# H21R20.net
KiCad netlist of a schematic drawn in EAGLE
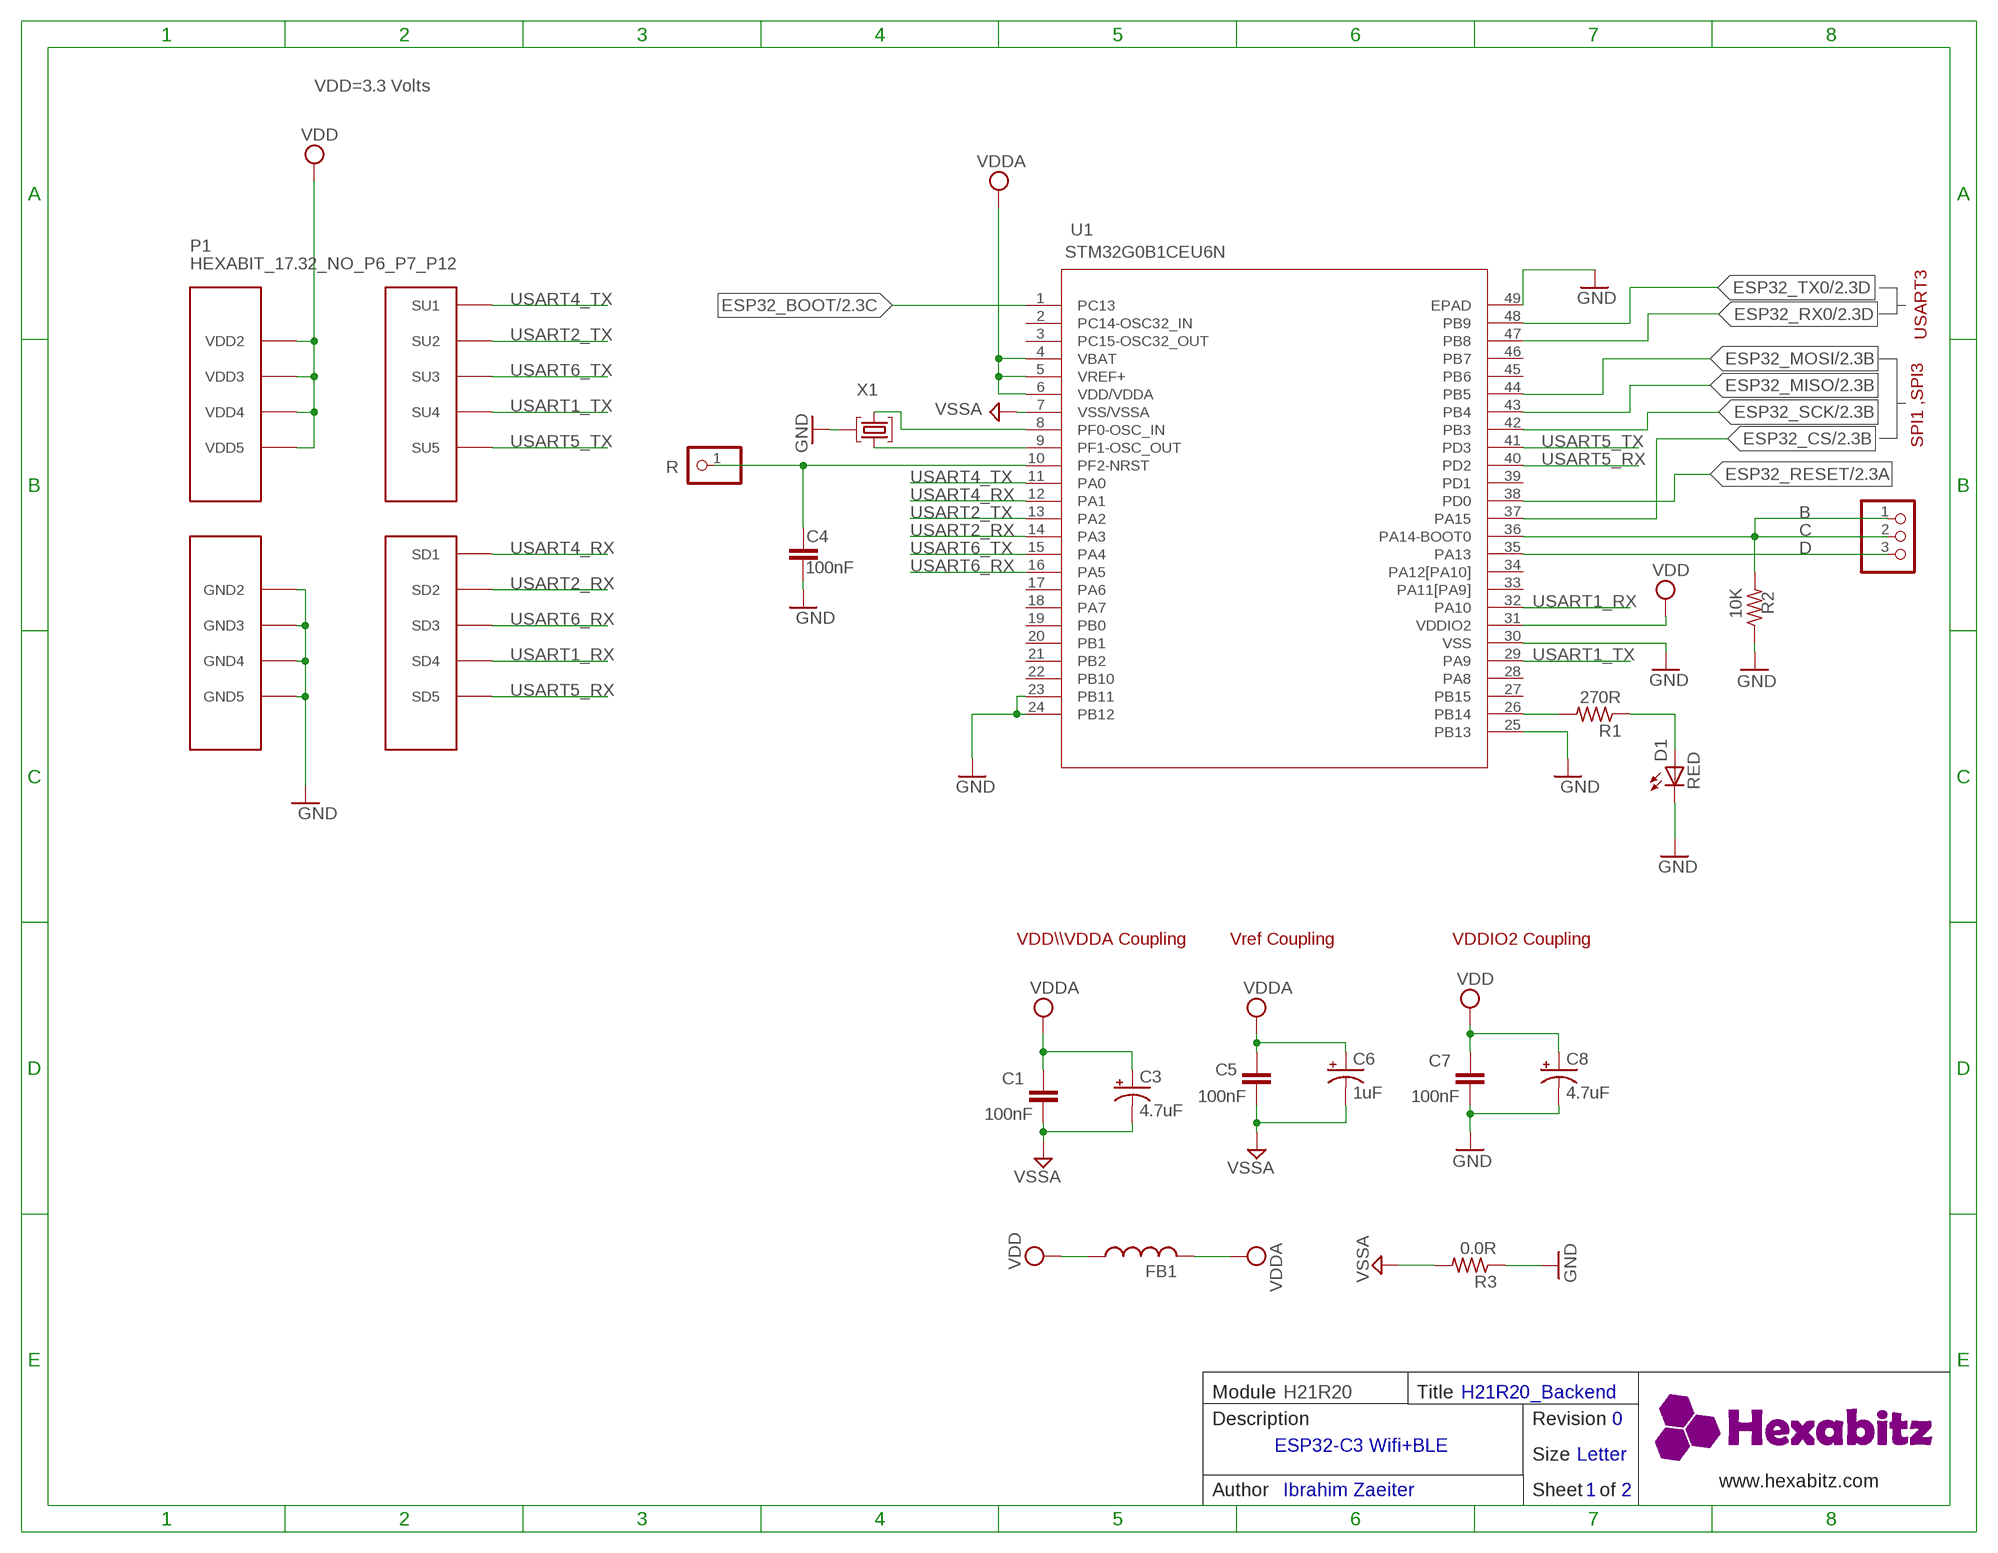
[diagram p0: schematic, sheet 1]
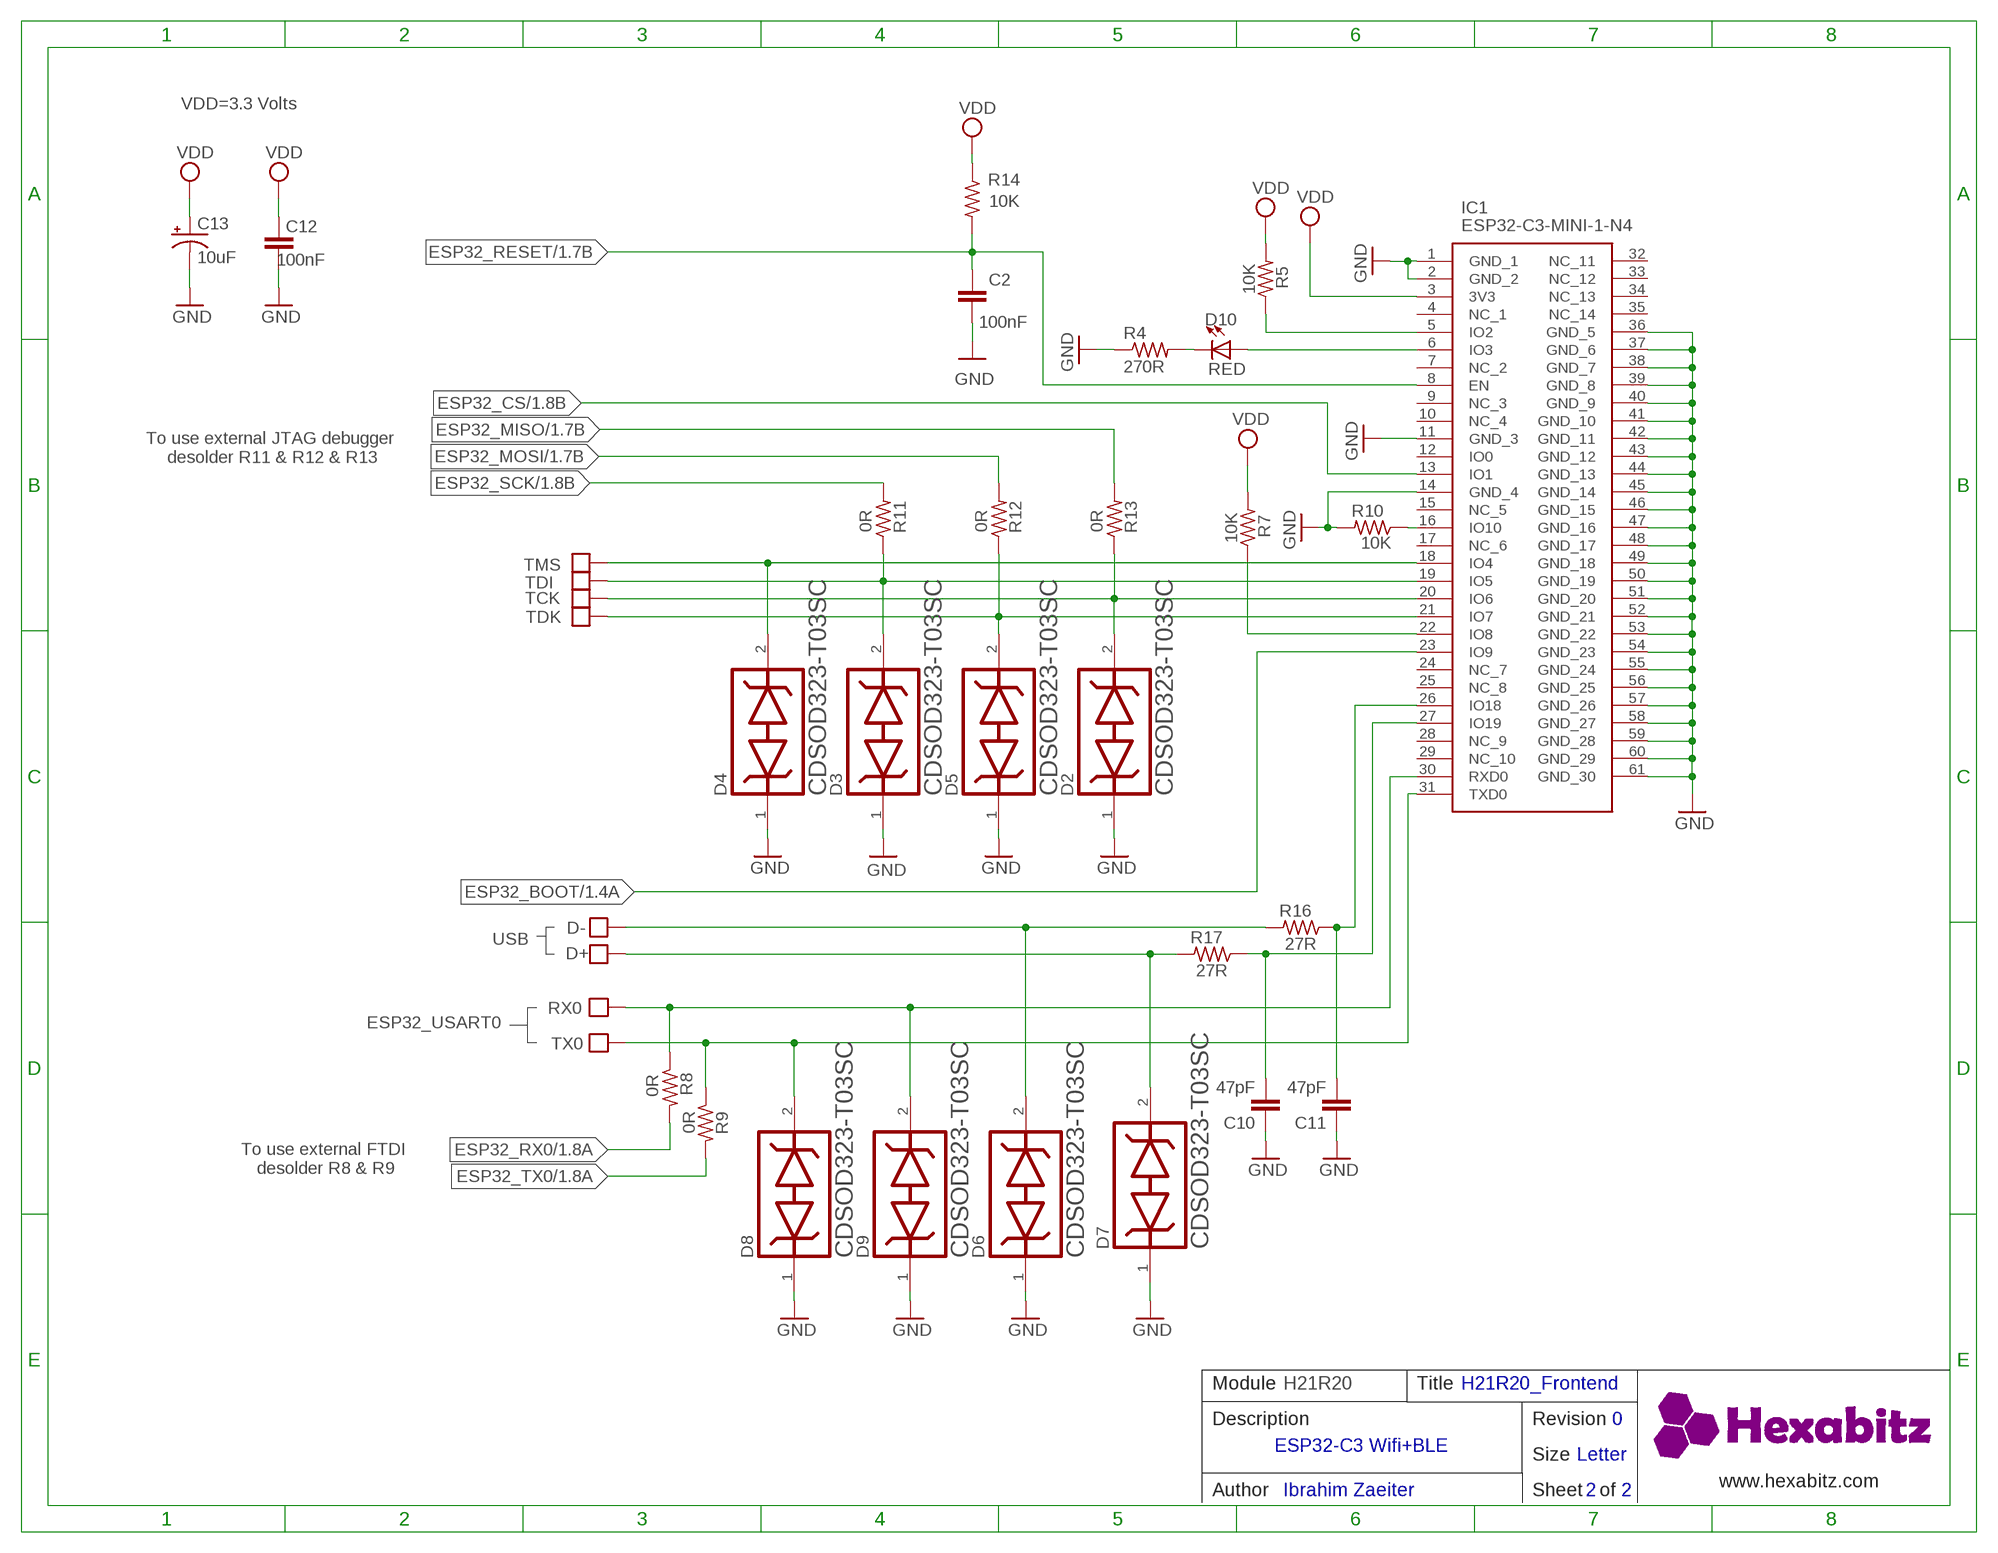
[diagram p1: schematic, sheet 2]

(export (version "E")
  (design (tool "Eeschema 10.0.6"))
  (components
    (comp (ref "C2")
      (value "100nF")
      (footprint "eagle-import:C-0603")
      (fields
        (field (name "CAPACITANCE") "100nF")
        (field (name "MFN") "AVX CORPORATION")
        (field (name "MPN") "'0603YC104K4T2A")
        (field (name "OCTOPART_URL") "'https://octopart.com/0603yc104k4t2a-avx+interconnect+%2F+elco-8120651")
        (field (name "TOLERANCE") "10%")
        (field (name "VOLTAGE_RATING") "16.0 V")
      )
      (libsource (lib "eagle-import") (part "C-0603"))
    )
    (comp (ref "C10")
      (value "47pF")
      (footprint "eagle-import:C-0603")
      (fields
        (field (name "CAPACITANCE") "100nF")
        (field (name "MFN") "AVX CORPORATION")
        (field (name "MPN") "'0603YC104K4T2A")
        (field (name "OCTOPART_URL") "'https://octopart.com/0603yc104k4t2a-avx+interconnect+%2F+elco-8120651")
        (field (name "TOLERANCE") "10%")
        (field (name "VOLTAGE_RATING") "16.0 V")
      )
      (libsource (lib "eagle-import") (part "C-0603"))
    )
    (comp (ref "C11")
      (value "47pF")
      (footprint "eagle-import:C-0603")
      (fields
        (field (name "CAPACITANCE") "100nF")
        (field (name "MFN") "AVX CORPORATION")
        (field (name "MPN") "'0603YC104K4T2A")
        (field (name "OCTOPART_URL") "'https://octopart.com/0603yc104k4t2a-avx+interconnect+%2F+elco-8120651")
        (field (name "TOLERANCE") "10%")
        (field (name "VOLTAGE_RATING") "16.0 V")
      )
      (libsource (lib "eagle-import") (part "C-0603"))
    )
    (comp (ref "C12")
      (value "100nF")
      (footprint "eagle-import:C-0603")
      (fields
        (field (name "CAPACITANCE") "100nF")
        (field (name "MFN") "AVX CORPORATION")
        (field (name "MPN") "'0603YC104K4T2A")
        (field (name "OCTOPART_URL") "'https://octopart.com/0603yc104k4t2a-avx+interconnect+%2F+elco-8120651")
        (field (name "TOLERANCE") "10%")
        (field (name "VOLTAGE_RATING") "16.0 V")
      )
      (libsource (lib "eagle-import") (part "C-0603"))
    )
    (comp (ref "C13")
      (value "10uF")
      (footprint "eagle-import:C-1210-POL")
      (libsource (lib "eagle-import") (part "C-1210-POL"))
    )
    (comp (ref "D+")
      (value "PAD4")
      (footprint "eagle-import:PAD4")
      (libsource (lib "eagle-import") (part "PAD4"))
    )
    (comp (ref "D-")
      (value "PAD4")
      (footprint "eagle-import:PAD4")
      (libsource (lib "eagle-import") (part "PAD4"))
    )
    (comp (ref "D2")
      (value "BOURNS_CDSOD323-T03SCBOURNS_CDSOD323-T03SC_0_0")
      (footprint "eagle-import:BOURNS_CDSOD323-T03SC_0")
      (fields (field (name "MPN") "CDSOD323-T03SC"))
      (libsource (lib "eagle-import") (part "BOURNS_CDSOD323-T03SCBOURNS_CDSOD323-T03SC_0_0"))
    )
    (comp (ref "D3")
      (value "BOURNS_CDSOD323-T03SCBOURNS_CDSOD323-T03SC_0_0")
      (footprint "eagle-import:BOURNS_CDSOD323-T03SC_0")
      (fields (field (name "MPN") "CDSOD323-T03SC"))
      (libsource (lib "eagle-import") (part "BOURNS_CDSOD323-T03SCBOURNS_CDSOD323-T03SC_0_0"))
    )
    (comp (ref "D4")
      (value "BOURNS_CDSOD323-T03SCBOURNS_CDSOD323-T03SC_0_0")
      (footprint "eagle-import:BOURNS_CDSOD323-T03SC_0")
      (fields (field (name "MPN") "CDSOD323-T03SC"))
      (libsource (lib "eagle-import") (part "BOURNS_CDSOD323-T03SCBOURNS_CDSOD323-T03SC_0_0"))
    )
    (comp (ref "D5")
      (value "BOURNS_CDSOD323-T03SCBOURNS_CDSOD323-T03SC_0_0")
      (footprint "eagle-import:BOURNS_CDSOD323-T03SC_0")
      (fields (field (name "MPN") "CDSOD323-T03SC"))
      (libsource (lib "eagle-import") (part "BOURNS_CDSOD323-T03SCBOURNS_CDSOD323-T03SC_0_0"))
    )
    (comp (ref "D6")
      (value "BOURNS_CDSOD323-T03SCBOURNS_CDSOD323-T03SC_0_0")
      (footprint "eagle-import:BOURNS_CDSOD323-T03SC_0")
      (fields (field (name "MPN") "CDSOD323-T03SC"))
      (libsource (lib "eagle-import") (part "BOURNS_CDSOD323-T03SCBOURNS_CDSOD323-T03SC_0_0"))
    )
    (comp (ref "D7")
      (value "BOURNS_CDSOD323-T03SCBOURNS_CDSOD323-T03SC_0_0")
      (footprint "eagle-import:BOURNS_CDSOD323-T03SC_0")
      (fields (field (name "MPN") "CDSOD323-T03SC"))
      (libsource (lib "eagle-import") (part "BOURNS_CDSOD323-T03SCBOURNS_CDSOD323-T03SC_0_0"))
    )
    (comp (ref "D8")
      (value "BOURNS_CDSOD323-T03SCBOURNS_CDSOD323-T03SC_0_0")
      (footprint "eagle-import:BOURNS_CDSOD323-T03SC_0")
      (fields (field (name "MPN") "CDSOD323-T03SC"))
      (libsource (lib "eagle-import") (part "BOURNS_CDSOD323-T03SCBOURNS_CDSOD323-T03SC_0_0"))
    )
    (comp (ref "D9")
      (value "BOURNS_CDSOD323-T03SCBOURNS_CDSOD323-T03SC_0_0")
      (footprint "eagle-import:BOURNS_CDSOD323-T03SC_0")
      (fields (field (name "MPN") "CDSOD323-T03SC"))
      (libsource (lib "eagle-import") (part "BOURNS_CDSOD323-T03SCBOURNS_CDSOD323-T03SC_0_0"))
    )
    (comp (ref "D10")
      (value "RED")
      (footprint "eagle-import:VLMS1300-GS08")
      (fields (field (name "MPN") "VLMS1300-GS08"))
      (libsource (lib "eagle-import") (part "VLMS1300-GS08"))
    )
    (comp (ref "IC1")
      (value "ESP32-C3-MINI-1-N4")
      (footprint "eagle-import:ESP32C3MINI1N4")
      (fields (field (name "MOUSER_PART_NUMBER") "356-ESP32-C3-MINI1N4"))
      (libsource (lib "eagle-import") (part "ESP32-C3-MINI-1-N4"))
    )
    (comp (ref "R4")
      (value "270R")
      (footprint "eagle-import:R-0603")
      (fields
        (field (name "MFN") "'Panasonic")
        (field (name "MPN") "'ERJ-3GEYJ271V")
        (field (name "OCTOPART_URL") "https://octopart.com/erj-3geyj271v-panasonic-55560546?r=sp")
        (field (name "RESISTANCE") "270R")
      )
      (libsource (lib "eagle-import") (part "R-0603"))
    )
    (comp (ref "R5")
      (value "10K")
      (footprint "eagle-import:R-0603")
      (fields
        (field (name "MFN") "YAGEO [VR]")
        (field (name "MPN") "RC0603JR-070RL")
        (field (name "OCTOPART_URL") "https://octopart.com/rc0603jr-070rl-yageo-1241539?r=sp")
        (field (name "RESISTANCE") "0R")
      )
      (libsource (lib "eagle-import") (part "R-0603"))
    )
    (comp (ref "R7")
      (value "10K")
      (footprint "eagle-import:R-0603")
      (fields
        (field (name "MFN") "YAGEO [VR]")
        (field (name "MPN") "RC0603JR-070RL")
        (field (name "OCTOPART_URL") "https://octopart.com/rc0603jr-070rl-yageo-1241539?r=sp")
        (field (name "RESISTANCE") "0R")
      )
      (libsource (lib "eagle-import") (part "R-0603"))
    )
    (comp (ref "R8")
      (value "0R")
      (footprint "eagle-import:R-0603")
      (fields
        (field (name "MFN") "YAGEO [VR]")
        (field (name "MPN") "RC0603JR-070RL")
        (field (name "OCTOPART_URL") "https://octopart.com/rc0603jr-070rl-yageo-1241539?r=sp")
        (field (name "RESISTANCE") "0R")
      )
      (libsource (lib "eagle-import") (part "R-0603"))
    )
    (comp (ref "R9")
      (value "0R")
      (footprint "eagle-import:R-0603")
      (fields
        (field (name "MFN") "YAGEO [VR]")
        (field (name "MPN") "RC0603JR-070RL")
        (field (name "OCTOPART_URL") "https://octopart.com/rc0603jr-070rl-yageo-1241539?r=sp")
        (field (name "RESISTANCE") "0R")
      )
      (libsource (lib "eagle-import") (part "R-0603"))
    )
    (comp (ref "R10")
      (value "10K")
      (footprint "eagle-import:R-0603")
      (fields
        (field (name "MFN") "YAGEO [VR]")
        (field (name "MPN") "RC0603JR-070RL")
        (field (name "OCTOPART_URL") "https://octopart.com/rc0603jr-070rl-yageo-1241539?r=sp")
        (field (name "RESISTANCE") "0R")
      )
      (libsource (lib "eagle-import") (part "R-0603"))
    )
    (comp (ref "R11")
      (value "0R")
      (footprint "eagle-import:R-0402")
      (fields
        (field (name "MFN") "YAGEO [VR]")
        (field (name "MPN") "RC0603JR-070RL")
        (field (name "OCTOPART_URL") "https://octopart.com/rc0603jr-070rl-yageo-1241539?r=sp")
        (field (name "RESISTANCE") "0R")
      )
      (libsource (lib "eagle-import") (part "R-0402"))
    )
    (comp (ref "R12")
      (value "0R")
      (footprint "eagle-import:R-0402")
      (fields
        (field (name "MFN") "YAGEO [VR]")
        (field (name "MPN") "RC0603JR-070RL")
        (field (name "OCTOPART_URL") "https://octopart.com/rc0603jr-070rl-yageo-1241539?r=sp")
        (field (name "RESISTANCE") "0R")
      )
      (libsource (lib "eagle-import") (part "R-0402"))
    )
    (comp (ref "R13")
      (value "0R")
      (footprint "eagle-import:R-0402")
      (fields
        (field (name "MFN") "YAGEO [VR]")
        (field (name "MPN") "RC0603JR-070RL")
        (field (name "OCTOPART_URL") "https://octopart.com/rc0603jr-070rl-yageo-1241539?r=sp")
        (field (name "RESISTANCE") "0R")
      )
      (libsource (lib "eagle-import") (part "R-0402"))
    )
    (comp (ref "R14")
      (value "10K")
      (footprint "eagle-import:R-0603")
      (fields
        (field (name "MFN") "YAGEO [VR]")
        (field (name "MPN") "RC0603JR-070RL")
        (field (name "OCTOPART_URL") "https://octopart.com/rc0603jr-070rl-yageo-1241539?r=sp")
        (field (name "RESISTANCE") "0R")
      )
      (libsource (lib "eagle-import") (part "R-0603"))
    )
    (comp (ref "R16")
      (value "27R")
      (footprint "eagle-import:R-0603")
      (fields
        (field (name "MFN") "YAGEO [VR]")
        (field (name "MPN") "RC0603JR-070RL")
        (field (name "OCTOPART_URL") "https://octopart.com/rc0603jr-070rl-yageo-1241539?r=sp")
        (field (name "RESISTANCE") "0R")
      )
      (libsource (lib "eagle-import") (part "R-0603"))
    )
    (comp (ref "R17")
      (value "27R")
      (footprint "eagle-import:R-0603")
      (fields
        (field (name "MFN") "YAGEO [VR]")
        (field (name "MPN") "RC0603JR-070RL")
        (field (name "OCTOPART_URL") "https://octopart.com/rc0603jr-070rl-yageo-1241539?r=sp")
        (field (name "RESISTANCE") "0R")
      )
      (libsource (lib "eagle-import") (part "R-0603"))
    )
    (comp (ref "RX0")
      (value "PAD4")
      (footprint "eagle-import:PAD4")
      (libsource (lib "eagle-import") (part "PAD4"))
    )
    (comp (ref "TCK")
      (value "PAD4")
      (footprint "eagle-import:PAD4")
      (libsource (lib "eagle-import") (part "PAD4"))
    )
    (comp (ref "TDI")
      (value "PAD4")
      (footprint "eagle-import:PAD4")
      (libsource (lib "eagle-import") (part "PAD4"))
    )
    (comp (ref "TDK")
      (value "PAD4")
      (footprint "eagle-import:PAD4")
      (libsource (lib "eagle-import") (part "PAD4"))
    )
    (comp (ref "TMS")
      (value "PAD4")
      (footprint "eagle-import:PAD4")
      (libsource (lib "eagle-import") (part "PAD4"))
    )
    (comp (ref "TX0")
      (value "PAD4")
      (footprint "eagle-import:PAD4")
      (libsource (lib "eagle-import") (part "PAD4"))
    )
    (comp (ref "C1")
      (value "100nF")
      (footprint "eagle-import:C-0603")
      (fields
        (field (name "CAPACITANCE") "100nF")
        (field (name "MFN") "AVX CORPORATION")
        (field (name "MPN") "'0603YC104K4T2A")
        (field (name "OCTOPART_URL") "'https://octopart.com/0603yc104k4t2a-avx+interconnect+%2F+elco-8120651")
        (field (name "TOLERANCE") "10%")
        (field (name "VOLTAGE_RATING") "16.0 V")
      )
      (libsource (lib "eagle-import") (part "C-0603"))
    )
    (comp (ref "C3")
      (value "4.7uF")
      (footprint "eagle-import:C-0805-POL")
      (fields
        (field (name "CAPACITANCE") "4.7uF")
        (field (name "MFN") "'Panasonic")
        (field (name "MPN") "'10TPU4R7MSI")
        (field (name "OCTOPART_URL") "https://octopart.com/10tpu4r7msi-panasonic-29487748?r=sp")
        (field (name "TOLERANCE") "20%")
        (field (name "VOLTAGE_RATING") "10.0 V")
      )
      (libsource (lib "eagle-import") (part "C-0805-POL"))
    )
    (comp (ref "C4")
      (value "100nF")
      (footprint "eagle-import:C-0603")
      (fields
        (field (name "CAPACITANCE") "100nF")
        (field (name "MFN") "AVX CORPORATION")
        (field (name "MPN") "0603YC104K4T2A")
        (field (name "OCTOPART_URL") "'https://octopart.com/0603yc104k4t2a-avx+interconnect+%2F+elco-8120651")
        (field (name "TOLERANCE") "10%")
        (field (name "VOLTAGE_RATING") "16.0 V")
      )
      (libsource (lib "eagle-import") (part "C-0603"))
    )
    (comp (ref "C5")
      (value "100nF")
      (footprint "eagle-import:C-0603")
      (fields
        (field (name "CAPACITANCE") "100nF")
        (field (name "MFN") "AVX CORPORATION")
        (field (name "MPN") "'0603YC104K4T2A")
        (field (name "OCTOPART_URL") "'https://octopart.com/0603yc104k4t2a-avx+interconnect+%2F+elco-8120651")
        (field (name "TOLERANCE") "10%")
        (field (name "VOLTAGE_RATING") "16.0 V")
      )
      (libsource (lib "eagle-import") (part "C-0603"))
    )
    (comp (ref "C6")
      (value "1uF")
      (footprint "eagle-import:C-0805-POL")
      (fields
        (field (name "CAPACITANCE") "4.7uF")
        (field (name "MFN") "'YAGEO [VA]")
        (field (name "MPN") "'CC0805KKX7R7BB105")
        (field (name "OCTOPART_URL") "'https://octopart.com/cc0805kkx7r7bb105-yageo-8376555?r=sp")
        (field (name "TOLERANCE") "20%")
        (field (name "VOLTAGE_RATING") "10.0 V")
      )
      (libsource (lib "eagle-import") (part "C-0805-POL"))
    )
    (comp (ref "C7")
      (value "100nF")
      (footprint "eagle-import:C-0603")
      (fields
        (field (name "CAPACITANCE") "100nF")
        (field (name "MFN") "AVX CORPORATION")
        (field (name "MPN") "'0603YC104K4T2A")
        (field (name "OCTOPART_URL") "'https://octopart.com/0603yc104k4t2a-avx+interconnect+%2F+elco-8120651")
        (field (name "TOLERANCE") "10%")
        (field (name "VOLTAGE_RATING") "16.0 V")
      )
      (libsource (lib "eagle-import") (part "C-0603"))
    )
    (comp (ref "C8")
      (value "4.7uF")
      (footprint "eagle-import:C-0805-POL")
      (fields
        (field (name "CAPACITANCE") "1.00uF")
        (field (name "MFN") "'Panasonic")
        (field (name "MPN") "'10TPU4R7MSI")
        (field (name "OCTOPART_URL") "https://octopart.com/10tpu4r7msi-panasonic-29487748?r=sp")
        (field (name "TOLERANCE") "10%")
        (field (name "VOLTAGE_RATING") "16.0 V")
      )
      (libsource (lib "eagle-import") (part "C-0805-POL"))
    )
    (comp (ref "D1")
      (value "RED")
      (footprint "eagle-import:VLMS1300-GS08")
      (fields (field (name "MPN") "VLMS1300-GS08"))
      (libsource (lib "eagle-import") (part "VLMS1300-GS08"))
    )
    (comp (ref "FB1")
      (value "FB-TDK_MMZ1608Y300B")
      (footprint "eagle-import:FB-TDK_MMZ1608Y300B")
      (fields
        (field (name "MFN") "TDK ")
        (field (name "MPN") "MMZ1608Y300BTA00")
        (field (name "OCTOPART_URL") "https://octopart.com/mmz1608y300bta00-tdk-7906990?r=sp")
      )
      (libsource (lib "eagle-import") (part "FB-TDK_MMZ1608Y300B"))
    )
    (comp (ref "JP1")
      (value "PINHD-1X3")
      (footprint "eagle-import:1X03")
      (libsource (lib "eagle-import") (part "PINHD-1X3"))
    )
    (comp (ref "P1")
      (value "HEXABIT_17.32_NO_P6_P7_P12")
      (footprint "eagle-import:HEXABIT_17.32_NO_P6_P7_P12")
      (libsource (lib "eagle-import") (part "HEXABIT_?_NO_P6_P7_P1217.32"))
    )
    (comp (ref "R")
      (value "PINHD-1X1")
      (footprint "eagle-import:1X01")
      (fields (field (name "MPN") "87227-1"))
      (libsource (lib "eagle-import") (part "PINHD-1X1"))
    )
    (comp (ref "R1")
      (value "270R")
      (footprint "eagle-import:R-0603")
      (fields
        (field (name "MFN") "'Panasonic")
        (field (name "MPN") "'ERJ-3GEYJ271V")
        (field (name "OCTOPART_URL") "https://octopart.com/erj-3geyj271v-panasonic-55560546?r=sp")
        (field (name "RESISTANCE") "270R")
      )
      (libsource (lib "eagle-import") (part "R-0603"))
    )
    (comp (ref "R2")
      (value "10K")
      (footprint "eagle-import:R-0603")
      (fields
        (field (name "MFN") "Vishay")
        (field (name "MPN") "'060300J0103T5E")
        (field (name "OCTOPART_URL") "https://octopart.com/search?q=060300J0103T5E&currency=USD&specs=0")
        (field (name "RESISTANCE") "10K")
      )
      (libsource (lib "eagle-import") (part "R-0603"))
    )
    (comp (ref "R3")
      (value "0.0R")
      (footprint "eagle-import:R-0603")
      (fields
        (field (name "MFN") "YAGEO [VR]")
        (field (name "MPN") "RC0603JR-070RL")
        (field (name "OCTOPART_URL") "https://octopart.com/rc0603jr-070rl-yageo-1241539?r=sp")
        (field (name "RESISTANCE") "0R")
      )
      (libsource (lib "eagle-import") (part "R-0603"))
    )
    (comp (ref "U1")
      (value "STM32G0B1CEU6N")
      (footprint "eagle-import:HEXABITZ_ICS_QFN_B1CEU6_STM-L")
      (libsource (lib "eagle-import") (part "STM32G0B1CEU6N"))
    )
    (comp (ref "X1")
      (value "8MHZ")
      (footprint "eagle-import:XTALL_CSTCE8M00G52")
      (fields
        (field (name "MPN") "CSTCE8M00G52Z-R0")
        (field (name "MPN_1") "CSTNE8M00G550000R0")
        (field (name "OCTOPART_URL") "https://octopart.com/cstne8m00g550000r0-murata-91406934?r=sp")
      )
      (libsource (lib "eagle-import") (part "XTALL_CSTCE8M00G52"))
    )
  )
  (nets
    (net (code "1") (name "C") (class "Default")
      (node (ref "JP1") (pin "1") (pinfunction "1_1") (pintype "passive"))
      (node (ref "JP1") (pin "2") (pinfunction "2_2") (pintype "passive"))
      (node (ref "R2") (pin "2") (pinfunction "2_2") (pintype "passive"))
      (node (ref "U1") (pin "36") (pinfunction "PA14-BOOT0_36") (pintype "bidirectional"))
    )
    (net (code "2") (name "D") (class "Default")
      (node (ref "JP1") (pin "3") (pinfunction "3_3") (pintype "passive"))
      (node (ref "U1") (pin "35") (pinfunction "PA13_35") (pintype "bidirectional"))
    )
    (net (code "3") (name "ESP32_BOOT") (class "Default")
      (node (ref "IC1") (pin "23") (pinfunction "IO9_23") (pintype "bidirectional"))
      (node (ref "U1") (pin "1") (pinfunction "PC13_1") (pintype "bidirectional"))
    )
    (net (code "4") (name "ESP32_CS") (class "Default")
      (node (ref "IC1") (pin "13") (pinfunction "IO1_13") (pintype "bidirectional"))
      (node (ref "U1") (pin "37") (pinfunction "PA15_37") (pintype "bidirectional"))
    )
    (net (code "5") (name "ESP32_MISO") (class "Default")
      (node (ref "R13") (pin "2") (pinfunction "2_2") (pintype "passive"))
      (node (ref "U1") (pin "43") (pinfunction "PB4_43") (pintype "bidirectional"))
    )
    (net (code "6") (name "ESP32_MOSI") (class "Default")
      (node (ref "R12") (pin "2") (pinfunction "2_2") (pintype "passive"))
      (node (ref "U1") (pin "44") (pinfunction "PB5_44") (pintype "bidirectional"))
    )
    (net (code "7") (name "ESP32_RESET") (class "Default")
      (node (ref "C2") (pin "2") (pinfunction "2_2") (pintype "passive"))
      (node (ref "IC1") (pin "8") (pinfunction "EN_8") (pintype "bidirectional"))
      (node (ref "R14") (pin "2") (pinfunction "2_2") (pintype "passive"))
      (node (ref "U1") (pin "38") (pinfunction "PD0_38") (pintype "bidirectional"))
    )
    (net (code "8") (name "ESP32_RX0") (class "Default")
      (node (ref "R8") (pin "2") (pinfunction "2_2") (pintype "passive"))
      (node (ref "U1") (pin "47") (pinfunction "PB8_47") (pintype "bidirectional"))
    )
    (net (code "9") (name "ESP32_SCK") (class "Default")
      (node (ref "R11") (pin "2") (pinfunction "2_2") (pintype "passive"))
      (node (ref "U1") (pin "42") (pinfunction "PB3_42") (pintype "bidirectional"))
    )
    (net (code "10") (name "ESP32_TX0") (class "Default")
      (node (ref "R9") (pin "2") (pinfunction "2_2") (pintype "passive"))
      (node (ref "U1") (pin "48") (pinfunction "PB9_48") (pintype "bidirectional"))
    )
    (net (code "11") (name "GND") (class "Default")
      (node (ref "C10") (pin "1") (pinfunction "1_1") (pintype "passive"))
      (node (ref "C11") (pin "1") (pinfunction "1_1") (pintype "passive"))
      (node (ref "C12") (pin "1") (pinfunction "1_1") (pintype "passive"))
      (node (ref "C13") (pin "2") (pinfunction "-_2") (pintype "passive"))
      (node (ref "C2") (pin "1") (pinfunction "1_1") (pintype "passive"))
      (node (ref "C4") (pin "1") (pinfunction "1_1") (pintype "passive"))
      (node (ref "C7") (pin "1") (pinfunction "1_1") (pintype "passive"))
      (node (ref "C8") (pin "2") (pinfunction "-_2") (pintype "passive"))
      (node (ref "D1") (pin "C") (pinfunction "C_C") (pintype "passive"))
      (node (ref "D2") (pin "1") (pinfunction "1_1") (pintype "bidirectional"))
      (node (ref "D3") (pin "1") (pinfunction "1_1") (pintype "bidirectional"))
      (node (ref "D4") (pin "1") (pinfunction "1_1") (pintype "bidirectional"))
      (node (ref "D5") (pin "1") (pinfunction "1_1") (pintype "bidirectional"))
      (node (ref "D6") (pin "1") (pinfunction "1_1") (pintype "bidirectional"))
      (node (ref "D7") (pin "1") (pinfunction "1_1") (pintype "bidirectional"))
      (node (ref "D8") (pin "1") (pinfunction "1_1") (pintype "bidirectional"))
      (node (ref "D9") (pin "1") (pinfunction "1_1") (pintype "bidirectional"))
      (node (ref "IC1") (pin "1") (pinfunction "GND_1_1") (pintype "bidirectional"))
      (node (ref "IC1") (pin "11") (pinfunction "GND_3_11") (pintype "bidirectional"))
      (node (ref "IC1") (pin "14") (pinfunction "GND_4_14") (pintype "bidirectional"))
      (node (ref "IC1") (pin "2") (pinfunction "GND_2_2") (pintype "bidirectional"))
      (node (ref "IC1") (pin "36") (pinfunction "GND_5_36") (pintype "bidirectional"))
      (node (ref "IC1") (pin "37") (pinfunction "GND_6_37") (pintype "bidirectional"))
      (node (ref "IC1") (pin "38") (pinfunction "GND_7_38") (pintype "bidirectional"))
      (node (ref "IC1") (pin "39") (pinfunction "GND_8_39") (pintype "bidirectional"))
      (node (ref "IC1") (pin "40") (pinfunction "GND_9_40") (pintype "bidirectional"))
      (node (ref "IC1") (pin "41") (pinfunction "GND_10_41") (pintype "bidirectional"))
      (node (ref "IC1") (pin "42") (pinfunction "GND_11_42") (pintype "bidirectional"))
      (node (ref "IC1") (pin "43") (pinfunction "GND_12_43") (pintype "bidirectional"))
      (node (ref "IC1") (pin "44") (pinfunction "GND_13_44") (pintype "bidirectional"))
      (node (ref "IC1") (pin "45") (pinfunction "GND_14_45") (pintype "bidirectional"))
      (node (ref "IC1") (pin "46") (pinfunction "GND_15_46") (pintype "bidirectional"))
      (node (ref "IC1") (pin "47") (pinfunction "GND_16_47") (pintype "bidirectional"))
      (node (ref "IC1") (pin "48") (pinfunction "GND_17_48") (pintype "bidirectional"))
      (node (ref "IC1") (pin "49") (pinfunction "GND_18_49") (pintype "bidirectional"))
      (node (ref "IC1") (pin "50") (pinfunction "GND_19_50") (pintype "bidirectional"))
      (node (ref "IC1") (pin "51") (pinfunction "GND_20_51") (pintype "bidirectional"))
      (node (ref "IC1") (pin "52") (pinfunction "GND_21_52") (pintype "bidirectional"))
      (node (ref "IC1") (pin "53") (pinfunction "GND_22_53") (pintype "bidirectional"))
      (node (ref "IC1") (pin "54") (pinfunction "GND_23_54") (pintype "bidirectional"))
      (node (ref "IC1") (pin "55") (pinfunction "GND_24_55") (pintype "bidirectional"))
      (node (ref "IC1") (pin "56") (pinfunction "GND_25_56") (pintype "bidirectional"))
      (node (ref "IC1") (pin "57") (pinfunction "GND_26_57") (pintype "bidirectional"))
      (node (ref "IC1") (pin "58") (pinfunction "GND_27_58") (pintype "bidirectional"))
      (node (ref "IC1") (pin "59") (pinfunction "GND_28_59") (pintype "bidirectional"))
      (node (ref "IC1") (pin "60") (pinfunction "GND_29_60") (pintype "bidirectional"))
      (node (ref "IC1") (pin "61") (pinfunction "GND_30_61") (pintype "bidirectional"))
      (node (ref "P1") (pin "PAD_PD10") (pinfunction "GND4_PAD_PD10") (pintype "power_in"))
      (node (ref "P1") (pin "PAD_PD11") (pinfunction "GND5_PAD_PD11") (pintype "power_in"))
      (node (ref "P1") (pin "PAD_PD8") (pinfunction "GND2_PAD_PD8") (pintype "power_in"))
      (node (ref "P1") (pin "PAD_PD9") (pinfunction "GND3_PAD_PD9") (pintype "power_in"))
      (node (ref "R10") (pin "2") (pinfunction "2_2") (pintype "passive"))
      (node (ref "R2") (pin "1") (pinfunction "1_1") (pintype "passive"))
      (node (ref "R3") (pin "1") (pinfunction "1_1") (pintype "passive"))
      (node (ref "R4") (pin "1") (pinfunction "1_1") (pintype "passive"))
      (node (ref "U1") (pin "23") (pinfunction "PB11_23") (pintype "bidirectional"))
      (node (ref "U1") (pin "24") (pinfunction "PB12_24") (pintype "bidirectional"))
      (node (ref "U1") (pin "25") (pinfunction "PB13_25") (pintype "bidirectional"))
      (node (ref "U1") (pin "30") (pinfunction "VSS_30") (pintype "passive"))
      (node (ref "U1") (pin "49") (pinfunction "EPAD_49") (pintype "passive"))
      (node (ref "X1") (pin "P$2") (pinfunction "2_P$2") (pintype "passive"))
    )
    (net (code "12") (name "Net-(D+-PadP$1)") (class "Default")
      (node (ref "D+") (pin "P$1") (pinfunction "P$1_P$1") (pintype "passive"))
      (node (ref "D7") (pin "2") (pinfunction "2_2") (pintype "bidirectional"))
      (node (ref "R17") (pin "2") (pinfunction "2_2") (pintype "passive"))
    )
    (net (code "13") (name "Net-(D--PadP$1)") (class "Default")
      (node (ref "D-") (pin "P$1") (pinfunction "P$1_P$1") (pintype "passive"))
      (node (ref "D6") (pin "2") (pinfunction "2_2") (pintype "bidirectional"))
      (node (ref "R16") (pin "2") (pinfunction "2_2") (pintype "passive"))
    )
    (net (code "14") (name "Net-(D1-PadA)") (class "Default")
      (node (ref "D1") (pin "A") (pinfunction "A_A") (pintype "passive"))
      (node (ref "R1") (pin "1") (pinfunction "1_1") (pintype "passive"))
    )
    (net (code "15") (name "Net-(D10-PadC)") (class "Default")
      (node (ref "D10") (pin "C") (pinfunction "C_C") (pintype "passive"))
      (node (ref "R4") (pin "2") (pinfunction "2_2") (pintype "passive"))
    )
    (net (code "16") (name "Net-(IC1-IO2)") (class "Default")
      (node (ref "IC1") (pin "5") (pinfunction "IO2_5") (pintype "bidirectional"))
      (node (ref "R5") (pin "1") (pinfunction "1_1") (pintype "passive"))
    )
    (net (code "17") (name "Net-(IC1-IO3)") (class "Default")
      (node (ref "D10") (pin "A") (pinfunction "A_A") (pintype "passive"))
      (node (ref "IC1") (pin "6") (pinfunction "IO3_6") (pintype "bidirectional"))
    )
    (net (code "18") (name "Net-(IC1-IO4)") (class "Default")
      (node (ref "D4") (pin "2") (pinfunction "2_2") (pintype "bidirectional"))
      (node (ref "IC1") (pin "18") (pinfunction "IO4_18") (pintype "bidirectional"))
      (node (ref "TMS") (pin "P$1") (pinfunction "P$1_P$1") (pintype "passive"))
    )
    (net (code "19") (name "Net-(IC1-IO5)") (class "Default")
      (node (ref "D3") (pin "2") (pinfunction "2_2") (pintype "bidirectional"))
      (node (ref "IC1") (pin "19") (pinfunction "IO5_19") (pintype "bidirectional"))
      (node (ref "R11") (pin "1") (pinfunction "1_1") (pintype "passive"))
      (node (ref "TDI") (pin "P$1") (pinfunction "P$1_P$1") (pintype "passive"))
    )
    (net (code "20") (name "Net-(IC1-IO6)") (class "Default")
      (node (ref "D2") (pin "2") (pinfunction "2_2") (pintype "bidirectional"))
      (node (ref "IC1") (pin "20") (pinfunction "IO6_20") (pintype "bidirectional"))
      (node (ref "R13") (pin "1") (pinfunction "1_1") (pintype "passive"))
      (node (ref "TCK") (pin "P$1") (pinfunction "P$1_P$1") (pintype "passive"))
    )
    (net (code "21") (name "Net-(IC1-IO7)") (class "Default")
      (node (ref "D5") (pin "2") (pinfunction "2_2") (pintype "bidirectional"))
      (node (ref "IC1") (pin "21") (pinfunction "IO7_21") (pintype "bidirectional"))
      (node (ref "R12") (pin "1") (pinfunction "1_1") (pintype "passive"))
      (node (ref "TDK") (pin "P$1") (pinfunction "P$1_P$1") (pintype "passive"))
    )
    (net (code "22") (name "Net-(IC1-IO8)") (class "Default")
      (node (ref "IC1") (pin "22") (pinfunction "IO8_22") (pintype "bidirectional"))
      (node (ref "R7") (pin "1") (pinfunction "1_1") (pintype "passive"))
    )
    (net (code "23") (name "Net-(IC1-IO10)") (class "Default")
      (node (ref "IC1") (pin "16") (pinfunction "IO10_16") (pintype "bidirectional"))
      (node (ref "R10") (pin "1") (pinfunction "1_1") (pintype "passive"))
    )
    (net (code "24") (name "Net-(IC1-IO18)") (class "Default")
      (node (ref "C11") (pin "2") (pinfunction "2_2") (pintype "passive"))
      (node (ref "IC1") (pin "26") (pinfunction "IO18_26") (pintype "bidirectional"))
      (node (ref "R16") (pin "1") (pinfunction "1_1") (pintype "passive"))
    )
    (net (code "25") (name "Net-(IC1-IO19)") (class "Default")
      (node (ref "C10") (pin "2") (pinfunction "2_2") (pintype "passive"))
      (node (ref "IC1") (pin "27") (pinfunction "IO19_27") (pintype "bidirectional"))
      (node (ref "R17") (pin "1") (pinfunction "1_1") (pintype "passive"))
    )
    (net (code "26") (name "Net-(IC1-RXD0)") (class "Default")
      (node (ref "D9") (pin "2") (pinfunction "2_2") (pintype "bidirectional"))
      (node (ref "IC1") (pin "30") (pinfunction "RXD0_30") (pintype "bidirectional"))
      (node (ref "R8") (pin "1") (pinfunction "1_1") (pintype "passive"))
      (node (ref "RX0") (pin "P$1") (pinfunction "P$1_P$1") (pintype "passive"))
    )
    (net (code "27") (name "Net-(IC1-TXD0)") (class "Default")
      (node (ref "D8") (pin "2") (pinfunction "2_2") (pintype "bidirectional"))
      (node (ref "IC1") (pin "31") (pinfunction "TXD0_31") (pintype "bidirectional"))
      (node (ref "R9") (pin "1") (pinfunction "1_1") (pintype "passive"))
      (node (ref "TX0") (pin "P$1") (pinfunction "P$1_P$1") (pintype "passive"))
    )
    (net (code "28") (name "Net-(U1-PB14)") (class "Default")
      (node (ref "R1") (pin "2") (pinfunction "2_2") (pintype "passive"))
      (node (ref "U1") (pin "26") (pinfunction "PB14_26") (pintype "bidirectional"))
    )
    (net (code "29") (name "Net-(U1-PF0-OSC_IN)") (class "Default")
      (node (ref "U1") (pin "8") (pinfunction "PF0-OSC_IN_8") (pintype "bidirectional"))
      (node (ref "X1") (pin "P$1") (pinfunction "1_P$1") (pintype "passive"))
    )
    (net (code "30") (name "Net-(U1-PF1-OSC_OUT)") (class "Default")
      (node (ref "U1") (pin "9") (pinfunction "PF1-OSC_OUT_9") (pintype "bidirectional"))
      (node (ref "X1") (pin "P$3") (pinfunction "3_P$3") (pintype "passive"))
    )
    (net (code "31") (name "Net-(U1-PF2-NRST)") (class "Default")
      (node (ref "C4") (pin "2") (pinfunction "2_2") (pintype "passive"))
      (node (ref "R") (pin "1") (pinfunction "1_1") (pintype "passive"))
      (node (ref "U1") (pin "10") (pinfunction "PF2-NRST_10") (pintype "bidirectional"))
    )
    (net (code "32") (name "USART1_RX") (class "Default")
      (node (ref "P1") (pin "PAD_PD4") (pinfunction "SD4_PAD_PD4") (pintype "bidirectional"))
      (node (ref "U1") (pin "32") (pinfunction "PA10_32") (pintype "bidirectional"))
    )
    (net (code "33") (name "USART1_TX") (class "Default")
      (node (ref "P1") (pin "PAD_PU4") (pinfunction "SU4_PAD_PU4") (pintype "bidirectional"))
      (node (ref "U1") (pin "29") (pinfunction "PA9_29") (pintype "bidirectional"))
    )
    (net (code "34") (name "USART2_RX") (class "Default")
      (node (ref "P1") (pin "PAD_PD2") (pinfunction "SD2_PAD_PD2") (pintype "bidirectional"))
      (node (ref "U1") (pin "14") (pinfunction "PA3_14") (pintype "bidirectional"))
    )
    (net (code "35") (name "USART2_TX") (class "Default")
      (node (ref "P1") (pin "PAD_PU2") (pinfunction "SU2_PAD_PU2") (pintype "bidirectional"))
      (node (ref "U1") (pin "13") (pinfunction "PA2_13") (pintype "bidirectional"))
    )
    (net (code "36") (name "USART4_RX") (class "Default")
      (node (ref "P1") (pin "PAD_PD1") (pinfunction "SD1_PAD_PD1") (pintype "bidirectional"))
      (node (ref "U1") (pin "12") (pinfunction "PA1_12") (pintype "bidirectional"))
    )
    (net (code "37") (name "USART4_TX") (class "Default")
      (node (ref "P1") (pin "PAD_PU1") (pinfunction "SU1_PAD_PU1") (pintype "bidirectional"))
      (node (ref "U1") (pin "11") (pinfunction "PA0_11") (pintype "bidirectional"))
    )
    (net (code "38") (name "USART5_RX") (class "Default")
      (node (ref "P1") (pin "PAD_PD5") (pinfunction "SD5_PAD_PD5") (pintype "bidirectional"))
      (node (ref "U1") (pin "40") (pinfunction "PD2_40") (pintype "bidirectional"))
    )
    (net (code "39") (name "USART5_TX") (class "Default")
      (node (ref "P1") (pin "PAD_PU5") (pinfunction "SU5_PAD_PU5") (pintype "bidirectional"))
      (node (ref "U1") (pin "41") (pinfunction "PD3_41") (pintype "bidirectional"))
    )
    (net (code "40") (name "USART6_RX") (class "Default")
      (node (ref "P1") (pin "PAD_PD3") (pinfunction "SD3_PAD_PD3") (pintype "bidirectional"))
      (node (ref "U1") (pin "16") (pinfunction "PA5_16") (pintype "bidirectional"))
    )
    (net (code "41") (name "USART6_TX") (class "Default")
      (node (ref "P1") (pin "PAD_PU3") (pinfunction "SU3_PAD_PU3") (pintype "bidirectional"))
      (node (ref "U1") (pin "15") (pinfunction "PA4_15") (pintype "bidirectional"))
    )
    (net (code "42") (name "VDD") (class "Default")
      (node (ref "C12") (pin "2") (pinfunction "2_2") (pintype "passive"))
      (node (ref "C13") (pin "1") (pinfunction "+_1") (pintype "passive"))
      (node (ref "C7") (pin "2") (pinfunction "2_2") (pintype "passive"))
      (node (ref "C8") (pin "1") (pinfunction "+_1") (pintype "passive"))
      (node (ref "FB1") (pin "1") (pinfunction "1_1") (pintype "passive"))
      (node (ref "IC1") (pin "3") (pinfunction "3V3_3") (pintype "bidirectional"))
      (node (ref "P1") (pin "PAD_PU10") (pinfunction "VDD4_PAD_PU10") (pintype "power_in"))
      (node (ref "P1") (pin "PAD_PU11") (pinfunction "VDD5_PAD_PU11") (pintype "power_in"))
      (node (ref "P1") (pin "PAD_PU8") (pinfunction "VDD2_PAD_PU8") (pintype "power_in"))
      (node (ref "P1") (pin "PAD_PU9") (pinfunction "VDD3_PAD_PU9") (pintype "power_in"))
      (node (ref "R14") (pin "1") (pinfunction "1_1") (pintype "passive"))
      (node (ref "R5") (pin "2") (pinfunction "2_2") (pintype "passive"))
      (node (ref "R7") (pin "2") (pinfunction "2_2") (pintype "passive"))
      (node (ref "U1") (pin "31") (pinfunction "VDDIO2_31") (pintype "power_in"))
    )
    (net (code "43") (name "VDDA") (class "Default")
      (node (ref "C1") (pin "2") (pinfunction "2_2") (pintype "passive"))
      (node (ref "C3") (pin "1") (pinfunction "+_1") (pintype "passive"))
      (node (ref "C5") (pin "2") (pinfunction "2_2") (pintype "passive"))
      (node (ref "C6") (pin "1") (pinfunction "+_1") (pintype "passive"))
      (node (ref "FB1") (pin "2") (pinfunction "2_2") (pintype "passive"))
      (node (ref "U1") (pin "4") (pinfunction "VBAT_4") (pintype "power_in"))
      (node (ref "U1") (pin "5") (pinfunction "VREF+_5") (pintype "power_in"))
      (node (ref "U1") (pin "6") (pinfunction "VDD/VDDA_6") (pintype "power_in"))
    )
    (net (code "44") (name "VSSA") (class "Default")
      (node (ref "C1") (pin "1") (pinfunction "1_1") (pintype "passive"))
      (node (ref "C3") (pin "2") (pinfunction "-_2") (pintype "passive"))
      (node (ref "C5") (pin "1") (pinfunction "1_1") (pintype "passive"))
      (node (ref "C6") (pin "2") (pinfunction "-_2") (pintype "passive"))
      (node (ref "R3") (pin "2") (pinfunction "2_2") (pintype "passive"))
      (node (ref "U1") (pin "7") (pinfunction "VSS/VSSA_7") (pintype "passive"))
    )
    (net (code "45") (name "unconnected-(IC1-IO0-Pad12)") (class "Default")
      (node (ref "IC1") (pin "12") (pinfunction "IO0_12") (pintype "bidirectional"))
    )
    (net (code "46") (name "unconnected-(IC1-NC_1-Pad4)") (class "Default")
      (node (ref "IC1") (pin "4") (pinfunction "NC_1_4") (pintype "bidirectional"))
    )
    (net (code "47") (name "unconnected-(IC1-NC_2-Pad7)") (class "Default")
      (node (ref "IC1") (pin "7") (pinfunction "NC_2_7") (pintype "bidirectional"))
    )
    (net (code "48") (name "unconnected-(IC1-NC_3-Pad9)") (class "Default")
      (node (ref "IC1") (pin "9") (pinfunction "NC_3_9") (pintype "bidirectional"))
    )
    (net (code "49") (name "unconnected-(IC1-NC_4-Pad10)") (class "Default")
      (node (ref "IC1") (pin "10") (pinfunction "NC_4_10") (pintype "bidirectional"))
    )
    (net (code "50") (name "unconnected-(IC1-NC_5-Pad15)") (class "Default")
      (node (ref "IC1") (pin "15") (pinfunction "NC_5_15") (pintype "bidirectional"))
    )
    (net (code "51") (name "unconnected-(IC1-NC_6-Pad17)") (class "Default")
      (node (ref "IC1") (pin "17") (pinfunction "NC_6_17") (pintype "bidirectional"))
    )
    (net (code "52") (name "unconnected-(IC1-NC_7-Pad24)") (class "Default")
      (node (ref "IC1") (pin "24") (pinfunction "NC_7_24") (pintype "bidirectional"))
    )
    (net (code "53") (name "unconnected-(IC1-NC_8-Pad25)") (class "Default")
      (node (ref "IC1") (pin "25") (pinfunction "NC_8_25") (pintype "bidirectional"))
    )
    (net (code "54") (name "unconnected-(IC1-NC_9-Pad28)") (class "Default")
      (node (ref "IC1") (pin "28") (pinfunction "NC_9_28") (pintype "bidirectional"))
    )
    (net (code "55") (name "unconnected-(IC1-NC_10-Pad29)") (class "Default")
      (node (ref "IC1") (pin "29") (pinfunction "NC_10_29") (pintype "bidirectional"))
    )
    (net (code "56") (name "unconnected-(IC1-NC_11-Pad32)") (class "Default")
      (node (ref "IC1") (pin "32") (pinfunction "NC_11_32") (pintype "bidirectional"))
    )
    (net (code "57") (name "unconnected-(IC1-NC_12-Pad33)") (class "Default")
      (node (ref "IC1") (pin "33") (pinfunction "NC_12_33") (pintype "bidirectional"))
    )
    (net (code "58") (name "unconnected-(IC1-NC_13-Pad34)") (class "Default")
      (node (ref "IC1") (pin "34") (pinfunction "NC_13_34") (pintype "bidirectional"))
    )
    (net (code "59") (name "unconnected-(IC1-NC_14-Pad35)") (class "Default")
      (node (ref "IC1") (pin "35") (pinfunction "NC_14_35") (pintype "bidirectional"))
    )
    (net (code "60") (name "unconnected-(U1-PA6-Pad17)") (class "Default")
      (node (ref "U1") (pin "17") (pinfunction "PA6_17") (pintype "bidirectional"))
    )
    (net (code "61") (name "unconnected-(U1-PA7-Pad18)") (class "Default")
      (node (ref "U1") (pin "18") (pinfunction "PA7_18") (pintype "bidirectional"))
    )
    (net (code "62") (name "unconnected-(U1-PA8-Pad28)") (class "Default")
      (node (ref "U1") (pin "28") (pinfunction "PA8_28") (pintype "bidirectional"))
    )
    (net (code "63") (name "unconnected-(U1-PA11[PA9]-Pad33)") (class "Default")
      (node (ref "U1") (pin "33") (pinfunction "PA11[PA9]_33") (pintype "bidirectional"))
    )
    (net (code "64") (name "unconnected-(U1-PA12[PA10]-Pad34)") (class "Default")
      (node (ref "U1") (pin "34") (pinfunction "PA12[PA10]_34") (pintype "bidirectional"))
    )
    (net (code "65") (name "unconnected-(U1-PB0-Pad19)") (class "Default")
      (node (ref "U1") (pin "19") (pinfunction "PB0_19") (pintype "bidirectional"))
    )
    (net (code "66") (name "unconnected-(U1-PB1-Pad20)") (class "Default")
      (node (ref "U1") (pin "20") (pinfunction "PB1_20") (pintype "bidirectional"))
    )
    (net (code "67") (name "unconnected-(U1-PB2-Pad21)") (class "Default")
      (node (ref "U1") (pin "21") (pinfunction "PB2_21") (pintype "bidirectional"))
    )
    (net (code "68") (name "unconnected-(U1-PB6-Pad45)") (class "Default")
      (node (ref "U1") (pin "45") (pinfunction "PB6_45") (pintype "bidirectional"))
    )
    (net (code "69") (name "unconnected-(U1-PB7-Pad46)") (class "Default")
      (node (ref "U1") (pin "46") (pinfunction "PB7_46") (pintype "bidirectional"))
    )
    (net (code "70") (name "unconnected-(U1-PB10-Pad22)") (class "Default")
      (node (ref "U1") (pin "22") (pinfunction "PB10_22") (pintype "bidirectional"))
    )
    (net (code "71") (name "unconnected-(U1-PB15-Pad27)") (class "Default")
      (node (ref "U1") (pin "27") (pinfunction "PB15_27") (pintype "bidirectional"))
    )
    (net (code "72") (name "unconnected-(U1-PC14-OSC32_IN-Pad2)") (class "Default")
      (node (ref "U1") (pin "2") (pinfunction "PC14-OSC32_IN_2") (pintype "bidirectional"))
    )
    (net (code "73") (name "unconnected-(U1-PC15-OSC32_OUT-Pad3)") (class "Default")
      (node (ref "U1") (pin "3") (pinfunction "PC15-OSC32_OUT_3") (pintype "bidirectional"))
    )
    (net (code "74") (name "unconnected-(U1-PD1-Pad39)") (class "Default")
      (node (ref "U1") (pin "39") (pinfunction "PD1_39") (pintype "bidirectional"))
    )
  )
)
